# Main.net
KiCad netlist of a schematic drawn in Altium Designer
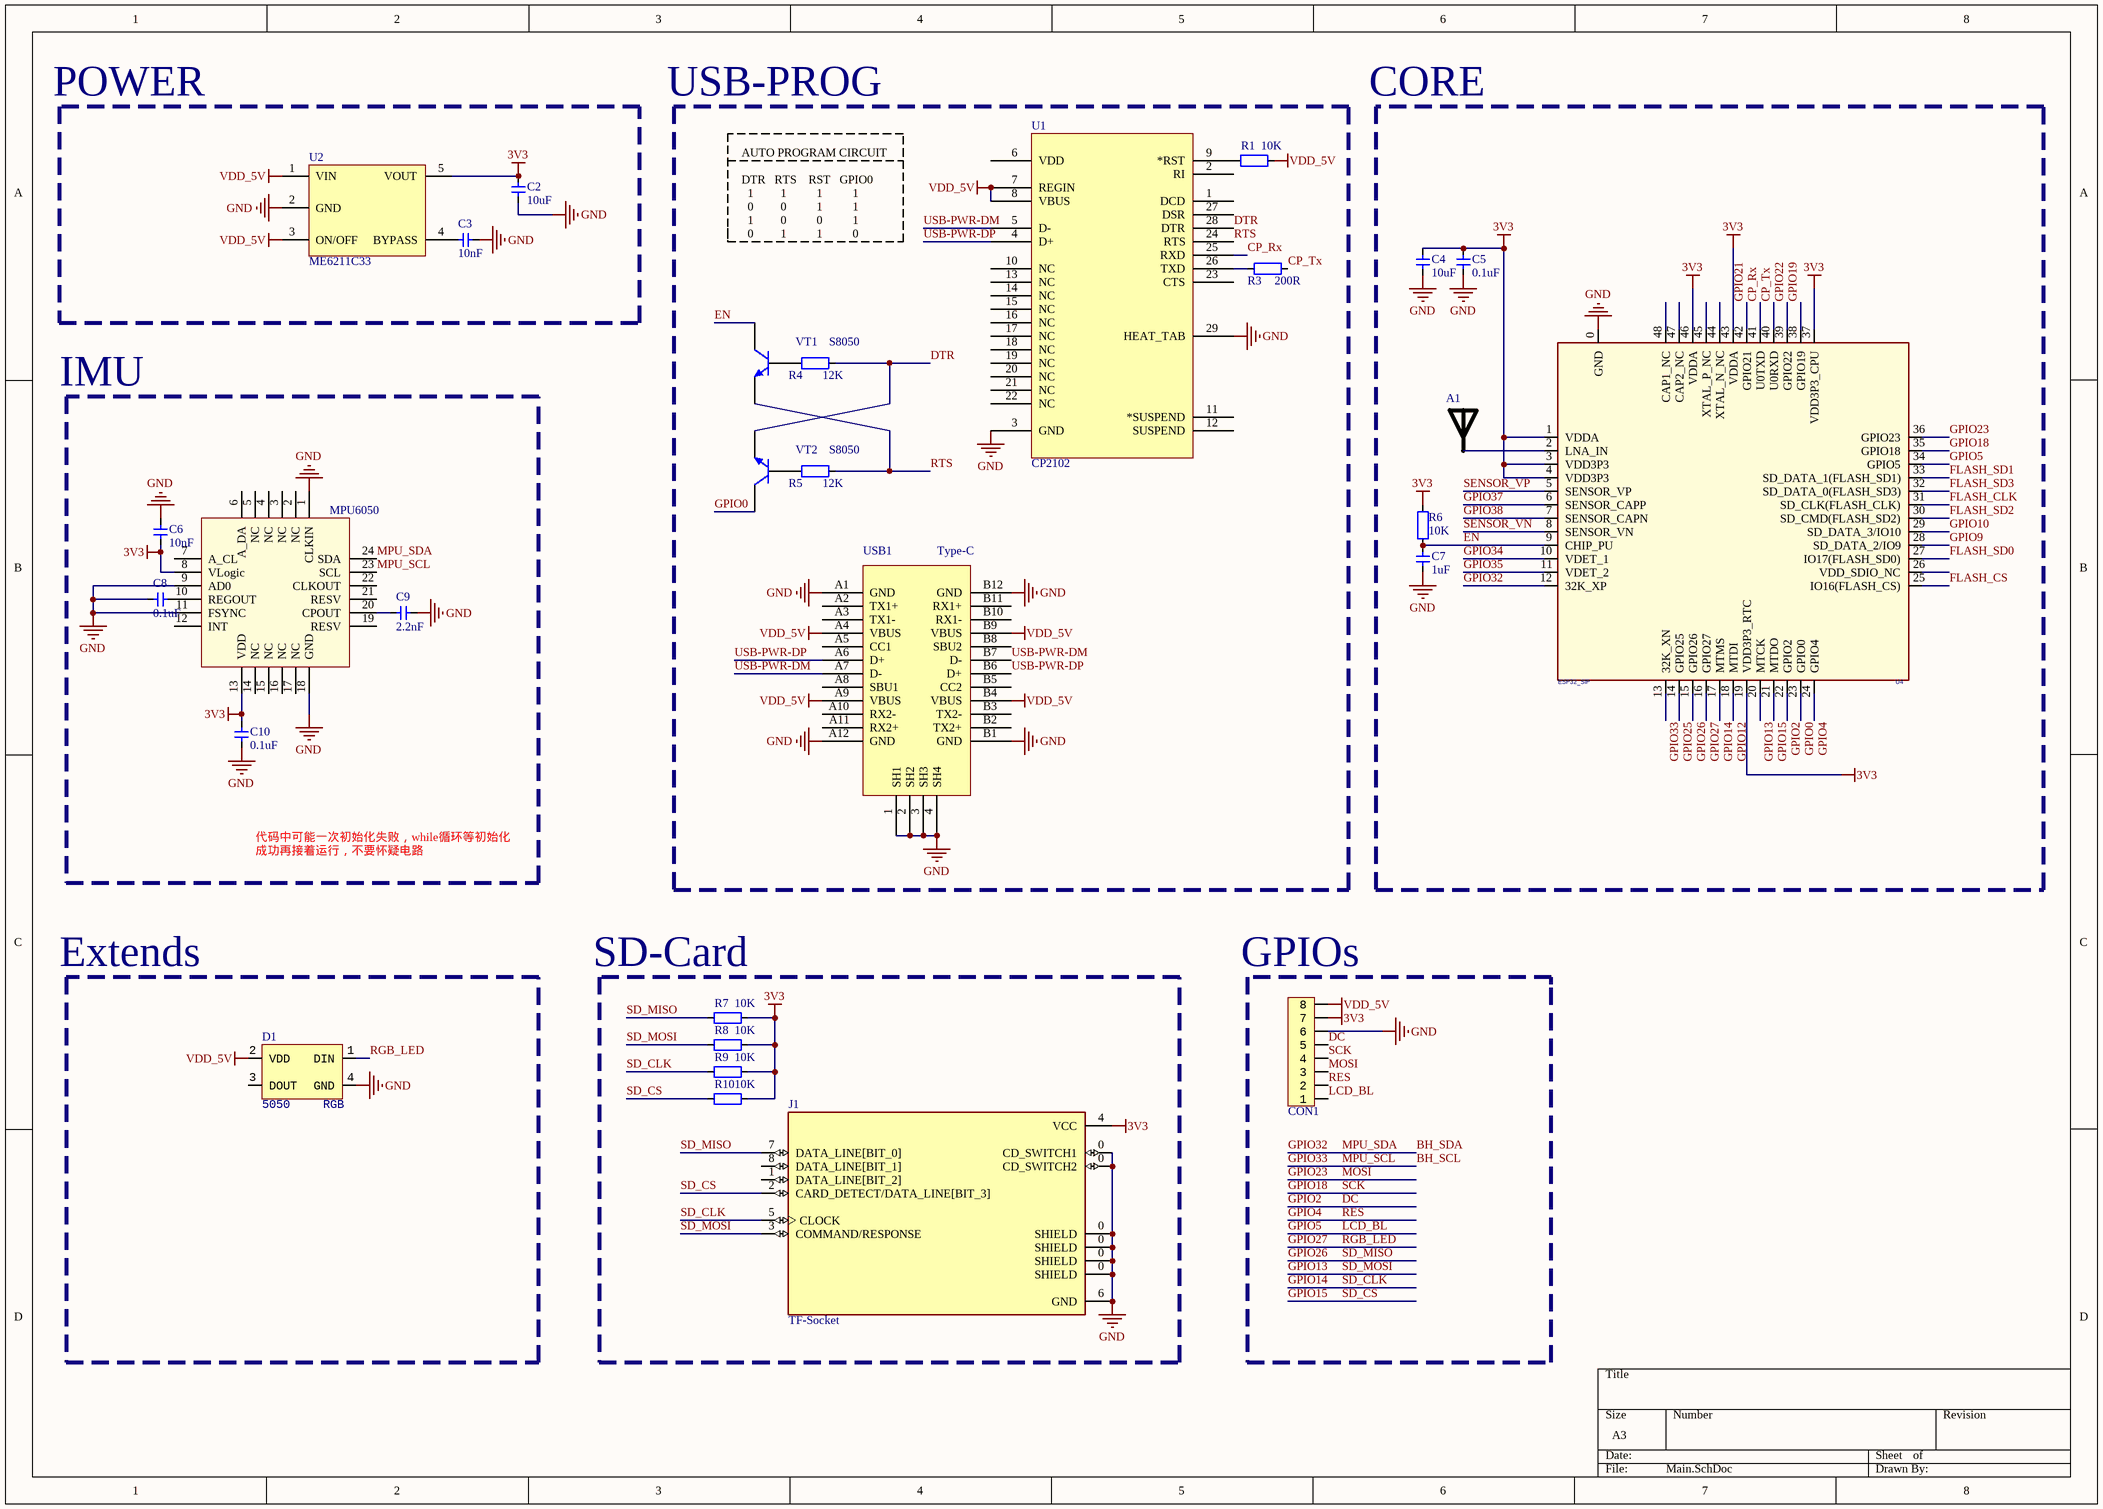
[diagram p0: Main.SchDoc]

(export (version "E")
  (design (tool "Eeschema 10.0.6"))
  (components
    (comp (ref "A1")
      (value "RAINSUN")
      (footprint "ANT-Rainsun-AN5120")
      (libsource (lib "MyPcbLib") (part "ANT-Rainsun-AP5120"))
    )
    (comp (ref "C2")
      (value "10uF")
      (footprint "CAP_0402")
      (description "Capacitor")
      (libsource (lib "MyPcbLib") (part "电容-0402"))
    )
    (comp (ref "C3")
      (value "10nF")
      (footprint "CAP_0402")
      (description "Capacitor")
      (libsource (lib "MyPcbLib") (part "电容-0402"))
    )
    (comp (ref "C4")
      (value "10uF")
      (footprint "CAP_0402")
      (description "Capacitor")
      (libsource (lib "MyPcbLib") (part "电容-0402"))
    )
    (comp (ref "C5")
      (value "0.1uF")
      (footprint "CAP_0402")
      (description "Capacitor")
      (libsource (lib "MyPcbLib") (part "电容-0402"))
    )
    (comp (ref "C6")
      (value "10nF")
      (footprint "CAP_0402")
      (description "Capacitor")
      (libsource (lib "MyPcbLib") (part "电容-0402"))
    )
    (comp (ref "C7")
      (value "1uF")
      (footprint "CAP_0402")
      (description "Capacitor")
      (libsource (lib "MyPcbLib") (part "电容-0402"))
    )
    (comp (ref "C8")
      (value "0.1uF")
      (footprint "CAP_0402")
      (description "Capacitor")
      (libsource (lib "MyPcbLib") (part "电容-0402"))
    )
    (comp (ref "C9")
      (value "2.2nF")
      (footprint "CAP_0402")
      (description "Capacitor")
      (libsource (lib "MyPcbLib") (part "电容-0402"))
    )
    (comp (ref "C10")
      (value "0.1uF")
      (footprint "CAP_0402")
      (description "Capacitor")
      (libsource (lib "MyPcbLib") (part "电容-0402"))
    )
    (comp (ref "CON1")
      (value "FFC_0.5_8")
      (footprint "FFC_0.5_8")
      (description "FFC")
      (libsource (lib "KitSprout") (part "FFC_0.5_8"))
    )
    (comp (ref "D1")
      (value "RGB")
      (footprint "LED_WS2812_CE")
      (description "LED")
      (fields (field (name "TYPE") "5050"))
      (libsource (lib "KitSprout") (part "LED_5050_WS2812B"))
    )
    (comp (ref "J1")
      (value "TF-Socket")
      (footprint "TF_F")
      (description "10 _8 + 2_ Position Card Connector Secure Digital - microSDâ„¢ Surface Mount, Right Angle Gold")
      (fields (field (name "MP") "1140084168") (field (name "MF") "Amphenol Commercial Products"))
      (libsource (lib "MyPcbLib") (part "TF-Socket"))
    )
    (comp (ref "R1")
      (value "10K")
      (footprint "RES_0402")
      (description "Resistor")
      (libsource (lib "MyPcbLib") (part "电阻-0402"))
    )
    (comp (ref "R3")
      (value "200R")
      (footprint "RES_0402")
      (description "Resistor")
      (libsource (lib "MyPcbLib") (part "电阻-0402"))
    )
    (comp (ref "R4")
      (value "12K")
      (footprint "RES_0402")
      (description "Resistor")
      (libsource (lib "MyPcbLib") (part "电阻-0402"))
    )
    (comp (ref "R5")
      (value "12K")
      (footprint "RES_0402")
      (description "Resistor")
      (libsource (lib "MyPcbLib") (part "电阻-0402"))
    )
    (comp (ref "R6")
      (value "10K")
      (footprint "RES_0402")
      (description "Resistor")
      (libsource (lib "") (part "电阻-0402_1"))
    )
    (comp (ref "R7")
      (value "10K")
      (footprint "RES_0402")
      (description "Resistor")
      (libsource (lib "MyPcbLib") (part "电阻-0402"))
    )
    (comp (ref "R8")
      (value "10K")
      (footprint "RES_0402")
      (description "Resistor")
      (libsource (lib "MyPcbLib") (part "电阻-0402"))
    )
    (comp (ref "R9")
      (value "10K")
      (footprint "RES_0402")
      (description "Resistor")
      (libsource (lib "MyPcbLib") (part "电阻-0402"))
    )
    (comp (ref "R10")
      (value "10K")
      (footprint "RES_0402")
      (description "Resistor")
      (libsource (lib "MyPcbLib") (part "电阻-0402"))
    )
    (comp (ref "U1")
      (value "CP2102")
      (footprint "QFN-28")
      (description "USB转TTL")
      (libsource (lib "mLib") (part "CP2102"))
    )
    (comp (ref "U2")
      (value "ME6211C33")
      (footprint "SOT23-5")
      (description "LDO")
      (libsource (lib "MyPcbLib") (part "LP2992"))
    )
    (comp (ref "U3")
      (value "MPU6050")
      (footprint "QFN-24")
      (description "六轴传感器")
      (libsource (lib "mLib") (part "MPU6050"))
    )
    (comp (ref "U4")
      (value "ESP32_SIP")
      (footprint "QFN-48_7X7")
      (libsource (lib "MyPcbLib") (part "ESP32-PICO"))
    )
    (comp (ref "USB1")
      (value "Type-C")
      (footprint "Type-C-TOP")
      (libsource (lib "MyPcbLib") (part "USB-Type-C-TOP"))
    )
    (comp (ref "VT1")
      (value "S8050")
      (footprint "SMT_TRIODE_NPN")
      (description "Surface mount NPN transistor, package SOT-23")
      (libsource (lib "MyPcbLib") (part "SMT_TRIODE_NPN"))
    )
    (comp (ref "VT2")
      (value "S8050")
      (footprint "SMT_TRIODE_NPN")
      (description "Surface mount NPN transistor, package SOT-23")
      (libsource (lib "MyPcbLib") (part "SMT_TRIODE_NPN"))
    )
  )
  (nets
    (net (code "1") (name "/BH_SCL") (class "Default")
      (node (ref "U3") (pin "23") (pinfunction "SCL_23") (pintype "passive"))
      (node (ref "U4") (pin "13") (pinfunction "32K_XN_13") (pintype "passive"))
    )
    (net (code "2") (name "/BH_SDA") (class "Default")
      (node (ref "U3") (pin "24") (pinfunction "SDA_24") (pintype "passive"))
      (node (ref "U4") (pin "12") (pinfunction "32K_XP_12") (pintype "passive"))
    )
    (net (code "3") (name "/CP_Rx") (class "Default")
      (node (ref "U1") (pin "25") (pinfunction "RXD_25") (pintype "passive"))
      (node (ref "U4") (pin "41") (pinfunction "U0TXD_41") (pintype "power_in"))
    )
    (net (code "4") (name "/CP_Tx") (class "Default")
      (node (ref "R3") (pin "1") (pinfunction "1_1") (pintype "passive"))
      (node (ref "U4") (pin "40") (pinfunction "U0RXD_40") (pintype "power_in"))
    )
    (net (code "5") (name "/DC") (class "Default")
      (node (ref "CON1") (pin "5") (pinfunction "5_5") (pintype "passive"))
      (node (ref "U4") (pin "22") (pinfunction "GPIO2_22") (pintype "passive"))
    )
    (net (code "6") (name "/DTR") (class "Default")
      (node (ref "R4") (pin "1") (pinfunction "1_1") (pintype "passive"))
      (node (ref "U1") (pin "28") (pinfunction "DTR_28") (pintype "passive"))
      (node (ref "VT2") (pin "2") (pinfunction "E_2") (pintype "passive"))
    )
    (net (code "7") (name "/EN") (class "Default")
      (node (ref "C7") (pin "1") (pinfunction "1_1") (pintype "passive"))
      (node (ref "R6") (pin "2") (pinfunction "2_2") (pintype "passive"))
      (node (ref "U4") (pin "9") (pinfunction "CHIP_PU_9") (pintype "passive"))
      (node (ref "VT1") (pin "3") (pinfunction "C_3") (pintype "passive"))
    )
    (net (code "8") (name "/FLASH_CLK") (class "Default")
      (node (ref "U4") (pin "31") (pinfunction "SD_CLK(FLASH_CLK)_31") (pintype "passive"))
    )
    (net (code "9") (name "/FLASH_CS") (class "Default")
      (node (ref "U4") (pin "25") (pinfunction "IO16(FLASH_CS)_25") (pintype "passive"))
    )
    (net (code "10") (name "/FLASH_SD0") (class "Default")
      (node (ref "U4") (pin "27") (pinfunction "IO17(FLASH_SD0)_27") (pintype "passive"))
    )
    (net (code "11") (name "/FLASH_SD1") (class "Default")
      (node (ref "U4") (pin "33") (pinfunction "SD_DATA_1(FLASH_SD1)_33") (pintype "passive"))
    )
    (net (code "12") (name "/FLASH_SD2") (class "Default")
      (node (ref "U4") (pin "30") (pinfunction "SD_CMD(FLASH_SD2)_30") (pintype "passive"))
    )
    (net (code "13") (name "/FLASH_SD3") (class "Default")
      (node (ref "U4") (pin "32") (pinfunction "SD_DATA_0(FLASH_SD3)_32") (pintype "passive"))
    )
    (net (code "14") (name "/GPIO0") (class "Default")
      (node (ref "U4") (pin "23") (pinfunction "GPIO0_23") (pintype "passive"))
      (node (ref "VT2") (pin "3") (pinfunction "C_3") (pintype "passive"))
    )
    (net (code "15") (name "/GPIO4") (class "Default")
      (node (ref "CON1") (pin "2") (pinfunction "2_2") (pintype "passive"))
      (node (ref "U4") (pin "24") (pinfunction "GPIO4_24") (pintype "passive"))
    )
    (net (code "16") (name "/GPIO5") (class "Default")
      (node (ref "CON1") (pin "1") (pinfunction "1_1") (pintype "passive"))
      (node (ref "U4") (pin "34") (pinfunction "GPIO5_34") (pintype "passive"))
    )
    (net (code "17") (name "/GPIO9") (class "Default")
      (node (ref "U4") (pin "28") (pinfunction "SD_DATA_2/IO9_28") (pintype "passive"))
    )
    (net (code "18") (name "/GPIO10") (class "Default")
      (node (ref "U4") (pin "29") (pinfunction "SD_DATA_3/IO10_29") (pintype "passive"))
    )
    (net (code "19") (name "/GPIO12") (class "Default")
      (node (ref "U4") (pin "18") (pinfunction "MTDI_18") (pintype "passive"))
    )
    (net (code "20") (name "/GPIO13") (class "Default")
      (node (ref "J1") (pin "3") (pinfunction "COMMAND/RESPONSE_3") (pintype "bidirectional"))
      (node (ref "R8") (pin "2") (pinfunction "2_2") (pintype "passive"))
      (node (ref "U4") (pin "20") (pinfunction "MTCK_20") (pintype "passive"))
    )
    (net (code "21") (name "/GPIO14") (class "Default")
      (node (ref "J1") (pin "5") (pinfunction "CLOCK_5") (pintype "bidirectional"))
      (node (ref "R9") (pin "2") (pinfunction "2_2") (pintype "passive"))
      (node (ref "U4") (pin "17") (pinfunction "MTMS_17") (pintype "passive"))
    )
    (net (code "22") (name "/GPIO15") (class "Default")
      (node (ref "J1") (pin "2") (pinfunction "CARD_DETECT/DATA_LINE[BIT_3]_2") (pintype "bidirectional"))
      (node (ref "R10") (pin "2") (pinfunction "2_2") (pintype "passive"))
      (node (ref "U4") (pin "21") (pinfunction "MTDO_21") (pintype "passive"))
    )
    (net (code "23") (name "/GPIO18") (class "Default")
      (node (ref "CON1") (pin "4") (pinfunction "4_4") (pintype "passive"))
      (node (ref "U4") (pin "35") (pinfunction "GPIO18_35") (pintype "passive"))
    )
    (net (code "24") (name "/GPIO19") (class "Default")
      (node (ref "U4") (pin "38") (pinfunction "GPIO19_38") (pintype "passive"))
    )
    (net (code "25") (name "/GPIO21") (class "Default")
      (node (ref "U4") (pin "42") (pinfunction "GPIO21_42") (pintype "passive"))
    )
    (net (code "26") (name "/GPIO22") (class "Default")
      (node (ref "U4") (pin "39") (pinfunction "GPIO22_39") (pintype "passive"))
    )
    (net (code "27") (name "/GPIO23") (class "Default")
      (node (ref "CON1") (pin "3") (pinfunction "3_3") (pintype "passive"))
      (node (ref "U4") (pin "36") (pinfunction "GPIO23_36") (pintype "passive"))
    )
    (net (code "28") (name "/GPIO25") (class "Default")
      (node (ref "U4") (pin "14") (pinfunction "GPIO25_14") (pintype "passive"))
    )
    (net (code "29") (name "/GPIO26") (class "Default")
      (node (ref "J1") (pin "7") (pinfunction "DATA_LINE[BIT_0]_7") (pintype "bidirectional"))
      (node (ref "R7") (pin "2") (pinfunction "2_2") (pintype "passive"))
      (node (ref "U4") (pin "15") (pinfunction "GPIO26_15") (pintype "passive"))
    )
    (net (code "30") (name "/GPIO27") (class "Default")
      (node (ref "D1") (pin "1") (pinfunction "DIN_1") (pintype "passive"))
      (node (ref "U4") (pin "16") (pinfunction "GPIO27_16") (pintype "passive"))
    )
    (net (code "31") (name "/GPIO34") (class "Default")
      (node (ref "U4") (pin "10") (pinfunction "VDET_1_10") (pintype "passive"))
    )
    (net (code "32") (name "/GPIO35") (class "Default")
      (node (ref "U4") (pin "11") (pinfunction "VDET_2_11") (pintype "passive"))
    )
    (net (code "33") (name "/GPIO37") (class "Default")
      (node (ref "U4") (pin "6") (pinfunction "SENSOR_CAPP_6") (pintype "passive"))
    )
    (net (code "34") (name "/GPIO38") (class "Default")
      (node (ref "U4") (pin "7") (pinfunction "SENSOR_CAPN_7") (pintype "passive"))
    )
    (net (code "35") (name "/RTS") (class "Default")
      (node (ref "R5") (pin "1") (pinfunction "1_1") (pintype "passive"))
      (node (ref "U1") (pin "24") (pinfunction "RTS_24") (pintype "passive"))
      (node (ref "VT1") (pin "2") (pinfunction "E_2") (pintype "passive"))
    )
    (net (code "36") (name "/SENSOR_VN") (class "Default")
      (node (ref "U4") (pin "8") (pinfunction "SENSOR_VN_8") (pintype "passive"))
    )
    (net (code "37") (name "/SENSOR_VP") (class "Default")
      (node (ref "U4") (pin "5") (pinfunction "SENSOR_VP_5") (pintype "passive"))
    )
    (net (code "38") (name "/USB-PWR-DM") (class "Default")
      (node (ref "U1") (pin "5") (pinfunction "D-_5") (pintype "passive"))
      (node (ref "USB1") (pin "A7") (pinfunction "D-_A7") (pintype "passive"))
      (node (ref "USB1") (pin "B7") (pinfunction "D-_B7") (pintype "passive"))
    )
    (net (code "39") (name "/USB-PWR-DP") (class "Default")
      (node (ref "U1") (pin "4") (pinfunction "D+_4") (pintype "passive"))
      (node (ref "USB1") (pin "A6") (pinfunction "D+_A6") (pintype "passive"))
      (node (ref "USB1") (pin "B6") (pinfunction "D+_B6") (pintype "passive"))
    )
    (net (code "40") (name "3V3") (class "Default")
      (node (ref "C10") (pin "2") (pinfunction "2_2") (pintype "passive"))
      (node (ref "C2") (pin "2") (pinfunction "2_2") (pintype "passive"))
      (node (ref "C4") (pin "2") (pinfunction "2_2") (pintype "passive"))
      (node (ref "C5") (pin "2") (pinfunction "2_2") (pintype "passive"))
      (node (ref "C6") (pin "1") (pinfunction "1_1") (pintype "passive"))
      (node (ref "CON1") (pin "7") (pinfunction "7_7") (pintype "passive"))
      (node (ref "J1") (pin "4") (pinfunction "VCC_4") (pintype "power_in"))
      (node (ref "R10") (pin "1") (pinfunction "1_1") (pintype "passive"))
      (node (ref "R6") (pin "1") (pinfunction "1_1") (pintype "passive"))
      (node (ref "R7") (pin "1") (pinfunction "1_1") (pintype "passive"))
      (node (ref "R8") (pin "1") (pinfunction "1_1") (pintype "passive"))
      (node (ref "R9") (pin "1") (pinfunction "1_1") (pintype "passive"))
      (node (ref "U2") (pin "5") (pinfunction "VOUT_5") (pintype "passive"))
      (node (ref "U3") (pin "13") (pinfunction "VDD_13") (pintype "passive"))
      (node (ref "U3") (pin "8") (pinfunction "VLogic_8") (pintype "passive"))
      (node (ref "U4") (pin "1") (pinfunction "VDDA_1") (pintype "power_in"))
      (node (ref "U4") (pin "19") (pinfunction "VDD3P3_RTC_19") (pintype "power_in"))
      (node (ref "U4") (pin "3") (pinfunction "VDD3P3_3") (pintype "power_in"))
      (node (ref "U4") (pin "37") (pinfunction "VDD3P3_CPU_37") (pintype "power_in"))
      (node (ref "U4") (pin "4") (pinfunction "VDD3P3_4") (pintype "power_in"))
      (node (ref "U4") (pin "43") (pinfunction "VDDA_43") (pintype "power_in"))
      (node (ref "U4") (pin "46") (pinfunction "VDDA_46") (pintype "power_in"))
    )
    (net (code "41") (name "GND") (class "Default")
      (node (ref "C10") (pin "1") (pinfunction "1_1") (pintype "passive"))
      (node (ref "C2") (pin "1") (pinfunction "1_1") (pintype "passive"))
      (node (ref "C3") (pin "1") (pinfunction "1_1") (pintype "passive"))
      (node (ref "C4") (pin "1") (pinfunction "1_1") (pintype "passive"))
      (node (ref "C5") (pin "1") (pinfunction "1_1") (pintype "passive"))
      (node (ref "C6") (pin "2") (pinfunction "2_2") (pintype "passive"))
      (node (ref "C7") (pin "2") (pinfunction "2_2") (pintype "passive"))
      (node (ref "C8") (pin "2") (pinfunction "2_2") (pintype "passive"))
      (node (ref "C9") (pin "1") (pinfunction "1_1") (pintype "passive"))
      (node (ref "CON1") (pin "6") (pinfunction "6_6") (pintype "passive"))
      (node (ref "D1") (pin "4") (pinfunction "GND_4") (pintype "passive"))
      (node (ref "J1") (pin "0") (pinfunction "SHIELD_0") (pintype "passive"))
      (node (ref "J1") (pin "6") (pinfunction "GND_6") (pintype "power_in"))
      (node (ref "U1") (pin "29") (pinfunction "HEAT_TAB_29") (pintype "passive"))
      (node (ref "U1") (pin "3") (pinfunction "GND_3") (pintype "passive"))
      (node (ref "U2") (pin "2") (pinfunction "GND_2") (pintype "passive"))
      (node (ref "U3") (pin "1") (pinfunction "CLKIN_1") (pintype "passive"))
      (node (ref "U3") (pin "11") (pinfunction "FSYNC_11") (pintype "passive"))
      (node (ref "U3") (pin "18") (pinfunction "GND_18") (pintype "passive"))
      (node (ref "U3") (pin "9") (pinfunction "AD0_9") (pintype "passive"))
      (node (ref "U4") (pin "0") (pinfunction "GND_0") (pintype "power_in"))
      (node (ref "USB1") (pin "1") (pinfunction "SH1_1") (pintype "passive"))
      (node (ref "USB1") (pin "2") (pinfunction "SH2_2") (pintype "passive"))
      (node (ref "USB1") (pin "3") (pinfunction "SH3_3") (pintype "passive"))
      (node (ref "USB1") (pin "4") (pinfunction "SH4_4") (pintype "passive"))
      (node (ref "USB1") (pin "A1") (pinfunction "GND_A1") (pintype "passive"))
      (node (ref "USB1") (pin "A12") (pinfunction "GND_A12") (pintype "passive"))
      (node (ref "USB1") (pin "B1") (pinfunction "GND_B1") (pintype "passive"))
      (node (ref "USB1") (pin "B12") (pinfunction "GND_B12") (pintype "passive"))
    )
    (net (code "42") (name "Net-(U1-*RST)") (class "Default")
      (node (ref "R1") (pin "2") (pinfunction "2_2") (pintype "passive"))
      (node (ref "U1") (pin "9") (pinfunction "*RST_9") (pintype "passive"))
    )
    (net (code "43") (name "Net-(U1-TXD)") (class "Default")
      (node (ref "R3") (pin "2") (pinfunction "2_2") (pintype "passive"))
      (node (ref "U1") (pin "26") (pinfunction "TXD_26") (pintype "passive"))
    )
    (net (code "44") (name "Net-(U2-BYPASS)") (class "Default")
      (node (ref "C3") (pin "2") (pinfunction "2_2") (pintype "passive"))
      (node (ref "U2") (pin "4") (pinfunction "BYPASS_4") (pintype "passive"))
    )
    (net (code "45") (name "Net-(U3-CPOUT)") (class "Default")
      (node (ref "C9") (pin "2") (pinfunction "2_2") (pintype "passive"))
      (node (ref "U3") (pin "20") (pinfunction "CPOUT_20") (pintype "passive"))
    )
    (net (code "46") (name "Net-(U3-REGOUT)") (class "Default")
      (node (ref "C8") (pin "1") (pinfunction "1_1") (pintype "passive"))
      (node (ref "U3") (pin "10") (pinfunction "REGOUT_10") (pintype "passive"))
    )
    (net (code "47") (name "Net-(U4-LNA_IN)") (class "Default")
      (node (ref "A1") (pin "1") (pinfunction "1_1") (pintype "passive"))
      (node (ref "U4") (pin "2") (pinfunction "LNA_IN_2") (pintype "passive"))
    )
    (net (code "48") (name "Net-(VT1-B)") (class "Default")
      (node (ref "R4") (pin "2") (pinfunction "2_2") (pintype "passive"))
      (node (ref "VT1") (pin "1") (pinfunction "B_1") (pintype "passive"))
    )
    (net (code "49") (name "Net-(VT2-B)") (class "Default")
      (node (ref "R5") (pin "2") (pinfunction "2_2") (pintype "passive"))
      (node (ref "VT2") (pin "1") (pinfunction "B_1") (pintype "passive"))
    )
    (net (code "50") (name "VDD_5V") (class "Default")
      (node (ref "CON1") (pin "8") (pinfunction "8_8") (pintype "passive"))
      (node (ref "D1") (pin "2") (pinfunction "VDD_2") (pintype "passive"))
      (node (ref "R1") (pin "1") (pinfunction "1_1") (pintype "passive"))
      (node (ref "U1") (pin "7") (pinfunction "REGIN_7") (pintype "passive"))
      (node (ref "U1") (pin "8") (pinfunction "VBUS_8") (pintype "passive"))
      (node (ref "U2") (pin "1") (pinfunction "VIN_1") (pintype "passive"))
      (node (ref "U2") (pin "3") (pinfunction "ON/OFF_3") (pintype "passive"))
      (node (ref "USB1") (pin "A4") (pinfunction "VBUS_A4") (pintype "passive"))
      (node (ref "USB1") (pin "A9") (pinfunction "VBUS_A9") (pintype "passive"))
      (node (ref "USB1") (pin "B4") (pinfunction "VBUS_B4") (pintype "passive"))
      (node (ref "USB1") (pin "B9") (pinfunction "VBUS_B9") (pintype "passive"))
    )
    (net (code "51") (name "unconnected-(D1-DOUT-Pad3)") (class "Default")
      (node (ref "D1") (pin "3") (pinfunction "DOUT_3") (pintype "passive"))
    )
    (net (code "52") (name "unconnected-(J1-DATA_LINE[BIT_1]-Pad8)") (class "Default")
      (node (ref "J1") (pin "8") (pinfunction "DATA_LINE[BIT_1]_8") (pintype "bidirectional"))
    )
    (net (code "53") (name "unconnected-(J1-DATA_LINE[BIT_2]-Pad1)") (class "Default")
      (node (ref "J1") (pin "1") (pinfunction "DATA_LINE[BIT_2]_1") (pintype "bidirectional"))
    )
    (net (code "54") (name "unconnected-(U1-*SUSPEND-Pad11)") (class "Default")
      (node (ref "U1") (pin "11") (pinfunction "*SUSPEND_11") (pintype "passive"))
    )
    (net (code "55") (name "unconnected-(U1-CTS-Pad23)") (class "Default")
      (node (ref "U1") (pin "23") (pinfunction "CTS_23") (pintype "passive"))
    )
    (net (code "56") (name "unconnected-(U1-DCD-Pad1)") (class "Default")
      (node (ref "U1") (pin "1") (pinfunction "DCD_1") (pintype "passive"))
    )
    (net (code "57") (name "unconnected-(U1-DSR-Pad27)") (class "Default")
      (node (ref "U1") (pin "27") (pinfunction "DSR_27") (pintype "passive"))
    )
    (net (code "58") (name "unconnected-(U1-NC-Pad10)") (class "Default")
      (node (ref "U1") (pin "10") (pinfunction "NC_10") (pintype "passive"))
    )
    (net (code "59") (name "unconnected-(U1-NC-Pad13)") (class "Default")
      (node (ref "U1") (pin "13") (pinfunction "NC_13") (pintype "passive"))
    )
    (net (code "60") (name "unconnected-(U1-NC-Pad14)") (class "Default")
      (node (ref "U1") (pin "14") (pinfunction "NC_14") (pintype "passive"))
    )
    (net (code "61") (name "unconnected-(U1-NC-Pad15)") (class "Default")
      (node (ref "U1") (pin "15") (pinfunction "NC_15") (pintype "passive"))
    )
    (net (code "62") (name "unconnected-(U1-NC-Pad16)") (class "Default")
      (node (ref "U1") (pin "16") (pinfunction "NC_16") (pintype "passive"))
    )
    (net (code "63") (name "unconnected-(U1-NC-Pad17)") (class "Default")
      (node (ref "U1") (pin "17") (pinfunction "NC_17") (pintype "passive"))
    )
    (net (code "64") (name "unconnected-(U1-NC-Pad18)") (class "Default")
      (node (ref "U1") (pin "18") (pinfunction "NC_18") (pintype "passive"))
    )
    (net (code "65") (name "unconnected-(U1-NC-Pad19)") (class "Default")
      (node (ref "U1") (pin "19") (pinfunction "NC_19") (pintype "passive"))
    )
    (net (code "66") (name "unconnected-(U1-NC-Pad20)") (class "Default")
      (node (ref "U1") (pin "20") (pinfunction "NC_20") (pintype "passive"))
    )
    (net (code "67") (name "unconnected-(U1-NC-Pad21)") (class "Default")
      (node (ref "U1") (pin "21") (pinfunction "NC_21") (pintype "passive"))
    )
    (net (code "68") (name "unconnected-(U1-NC-Pad22)") (class "Default")
      (node (ref "U1") (pin "22") (pinfunction "NC_22") (pintype "passive"))
    )
    (net (code "69") (name "unconnected-(U1-RI-Pad2)") (class "Default")
      (node (ref "U1") (pin "2") (pinfunction "RI_2") (pintype "passive"))
    )
    (net (code "70") (name "unconnected-(U1-SUSPEND-Pad12)") (class "Default")
      (node (ref "U1") (pin "12") (pinfunction "SUSPEND_12") (pintype "passive"))
    )
    (net (code "71") (name "unconnected-(U1-VDD-Pad6)") (class "Default")
      (node (ref "U1") (pin "6") (pinfunction "VDD_6") (pintype "passive"))
    )
    (net (code "72") (name "unconnected-(U3-A_CL-Pad7)") (class "Default")
      (node (ref "U3") (pin "7") (pinfunction "A_CL_7") (pintype "passive"))
    )
    (net (code "73") (name "unconnected-(U3-A_DA-Pad6)") (class "Default")
      (node (ref "U3") (pin "6") (pinfunction "A_DA_6") (pintype "passive"))
    )
    (net (code "74") (name "unconnected-(U3-CLKOUT-Pad22)") (class "Default")
      (node (ref "U3") (pin "22") (pinfunction "CLKOUT_22") (pintype "passive"))
    )
    (net (code "75") (name "unconnected-(U3-INT-Pad12)") (class "Default")
      (node (ref "U3") (pin "12") (pinfunction "INT_12") (pintype "passive"))
    )
    (net (code "76") (name "unconnected-(U3-NC-Pad2)") (class "Default")
      (node (ref "U3") (pin "2") (pinfunction "NC_2") (pintype "passive"))
    )
    (net (code "77") (name "unconnected-(U3-NC-Pad3)") (class "Default")
      (node (ref "U3") (pin "3") (pinfunction "NC_3") (pintype "passive"))
    )
    (net (code "78") (name "unconnected-(U3-NC-Pad4)") (class "Default")
      (node (ref "U3") (pin "4") (pinfunction "NC_4") (pintype "passive"))
    )
    (net (code "79") (name "unconnected-(U3-NC-Pad5)") (class "Default")
      (node (ref "U3") (pin "5") (pinfunction "NC_5") (pintype "passive"))
    )
    (net (code "80") (name "unconnected-(U3-NC-Pad14)") (class "Default")
      (node (ref "U3") (pin "14") (pinfunction "NC_14") (pintype "passive"))
    )
    (net (code "81") (name "unconnected-(U3-NC-Pad15)") (class "Default")
      (node (ref "U3") (pin "15") (pinfunction "NC_15") (pintype "passive"))
    )
    (net (code "82") (name "unconnected-(U3-NC-Pad16)") (class "Default")
      (node (ref "U3") (pin "16") (pinfunction "NC_16") (pintype "passive"))
    )
    (net (code "83") (name "unconnected-(U3-NC-Pad17)") (class "Default")
      (node (ref "U3") (pin "17") (pinfunction "NC_17") (pintype "passive"))
    )
    (net (code "84") (name "unconnected-(U3-RESV-Pad19)") (class "Default")
      (node (ref "U3") (pin "19") (pinfunction "RESV_19") (pintype "passive"))
    )
    (net (code "85") (name "unconnected-(U3-RESV-Pad21)") (class "Default")
      (node (ref "U3") (pin "21") (pinfunction "RESV_21") (pintype "passive"))
    )
    (net (code "86") (name "unconnected-(U4-CAP1_NC-Pad48)") (class "Default")
      (node (ref "U4") (pin "48") (pinfunction "CAP1_NC_48") (pintype "passive"))
    )
    (net (code "87") (name "unconnected-(U4-CAP2_NC-Pad47)") (class "Default")
      (node (ref "U4") (pin "47") (pinfunction "CAP2_NC_47") (pintype "passive"))
    )
    (net (code "88") (name "unconnected-(U4-VDD_SDIO_NC-Pad26)") (class "Default")
      (node (ref "U4") (pin "26") (pinfunction "VDD_SDIO_NC_26") (pintype "passive"))
    )
    (net (code "89") (name "unconnected-(U4-XTAL_N_NC-Pad44)") (class "Default")
      (node (ref "U4") (pin "44") (pinfunction "XTAL_N_NC_44") (pintype "passive"))
    )
    (net (code "90") (name "unconnected-(U4-XTAL_P_NC-Pad45)") (class "Default")
      (node (ref "U4") (pin "45") (pinfunction "XTAL_P_NC_45") (pintype "passive"))
    )
    (net (code "91") (name "unconnected-(USB1-CC1-PadA5)") (class "Default")
      (node (ref "USB1") (pin "A5") (pinfunction "CC1_A5") (pintype "passive"))
    )
    (net (code "92") (name "unconnected-(USB1-CC2-PadB5)") (class "Default")
      (node (ref "USB1") (pin "B5") (pinfunction "CC2_B5") (pintype "passive"))
    )
    (net (code "93") (name "unconnected-(USB1-RX1+-PadB11)") (class "Default")
      (node (ref "USB1") (pin "B11") (pinfunction "RX1+_B11") (pintype "passive"))
    )
    (net (code "94") (name "unconnected-(USB1-RX1--PadB10)") (class "Default")
      (node (ref "USB1") (pin "B10") (pinfunction "RX1-_B10") (pintype "passive"))
    )
    (net (code "95") (name "unconnected-(USB1-RX2+-PadA11)") (class "Default")
      (node (ref "USB1") (pin "A11") (pinfunction "RX2+_A11") (pintype "passive"))
    )
    (net (code "96") (name "unconnected-(USB1-RX2--PadA10)") (class "Default")
      (node (ref "USB1") (pin "A10") (pinfunction "RX2-_A10") (pintype "passive"))
    )
    (net (code "97") (name "unconnected-(USB1-SBU1-PadA8)") (class "Default")
      (node (ref "USB1") (pin "A8") (pinfunction "SBU1_A8") (pintype "passive"))
    )
    (net (code "98") (name "unconnected-(USB1-SBU2-PadB8)") (class "Default")
      (node (ref "USB1") (pin "B8") (pinfunction "SBU2_B8") (pintype "passive"))
    )
    (net (code "99") (name "unconnected-(USB1-TX1+-PadA2)") (class "Default")
      (node (ref "USB1") (pin "A2") (pinfunction "TX1+_A2") (pintype "passive"))
    )
    (net (code "100") (name "unconnected-(USB1-TX1--PadA3)") (class "Default")
      (node (ref "USB1") (pin "A3") (pinfunction "TX1-_A3") (pintype "passive"))
    )
    (net (code "101") (name "unconnected-(USB1-TX2+-PadB2)") (class "Default")
      (node (ref "USB1") (pin "B2") (pinfunction "TX2+_B2") (pintype "passive"))
    )
    (net (code "102") (name "unconnected-(USB1-TX2--PadB3)") (class "Default")
      (node (ref "USB1") (pin "B3") (pinfunction "TX2-_B3") (pintype "passive"))
    )
  )
)
